# Wi-Fi.net
KiCad netlist of a schematic drawn in Altium Designer
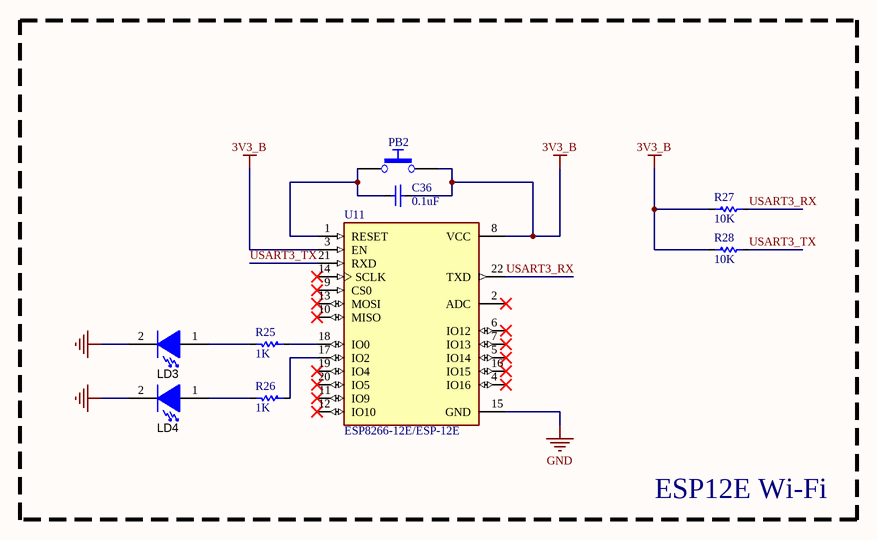
[diagram p0: Wi-Fi.SchDoc]

(export (version "E")
  (design (tool "Eeschema 10.0.6"))
  (components
    (comp (ref "C36")
      (value "0.1uF")
      (footprint "CAPC1608-0603X85N")
      (description "CAP CER 0.1UF 25V X7R 0603")
      (fields (field (name "MANUFACTURER") "Yageo") (field (name "VOLTAGE") "25V"))
      (libsource (lib "capacitor") (part "Capacitor Ceramic"))
    )
    (comp (ref "LD3")
      (value "160-1183-1-ND")
      (footprint "LED_LTST-C190")
      (description "LED, Green, SMD")
      (libsource (lib "LED") (part "LTST-C190GKT"))
    )
    (comp (ref "LD4")
      (value "160-1183-1-ND")
      (footprint "LED_LTST-C190")
      (description "LED, Green, SMD")
      (libsource (lib "LED") (part "LTST-C190GKT"))
    )
    (comp (ref "PB2")
      (value "Push Button")
      (footprint "PB_TYCO_FSMSM")
      (description "Push-Button Switch SPDT")
      (fields
        (field (name "PART NUMBER") "PB_TYCO_FSMSM")
        (field (name "MANUFACTURER") "TYCO ELECTRONICS")
        (field (name "AUTHOR") "CERN DEM JLC")
      )
      (libsource (lib "Eletro-mechanical") (part "PB SPST 1NO-2NO"))
    )
    (comp (ref "R25")
      (value "1K")
      (footprint "RESC1608-0603X50N")
      (description "RES SMD 1K OHM 1% 1/10W 0603")
      (fields (field (name "MANUFACTURER") "Panasonic Electronic Components") (field (name "TOLERANCE") "1%"))
      (libsource (lib "resistor") (part "Resistor SMD"))
    )
    (comp (ref "R26")
      (value "1K")
      (footprint "RESC1608-0603X50N")
      (description "RES SMD 1K OHM 1% 1/10W 0603")
      (fields (field (name "MANUFACTURER") "Panasonic Electronic Components") (field (name "TOLERANCE") "1%"))
      (libsource (lib "resistor") (part "Resistor SMD"))
    )
    (comp (ref "R27")
      (value "10K")
      (footprint "RESC1608-0603X50N")
      (description "RES SMD 10K OHM 1% 1/10W 0603")
      (fields (field (name "MANUFACTURER") "Yageo"))
      (libsource (lib "ANTSIS_PASSIVE") (part "RESISTOR 10K"))
    )
    (comp (ref "R28")
      (value "10K")
      (footprint "RESC1608-0603X50N")
      (description "RES SMD 10K OHM 1% 1/10W 0603")
      (fields (field (name "MANUFACTURER") "Yageo"))
      (libsource (lib "ANTSIS_PASSIVE") (part "RESISTOR 10K"))
    )
    (comp (ref "U11")
      (value "ESP8266-12E/ESP-12E")
      (footprint "XCVR_ESP8266-12E/ESP-12E")
      (fields (field (name "MF") "AI-Thinker"))
      (libsource (lib "ESP8266-12E_ESP-12E") (part "ESP8266-12E/ESP-12E"))
    )
  )
  (nets
    (net (code "1") (name "/USART3_RX") (class "Default")
      (node (ref "R27") (pin "2") (pinfunction "2_2") (pintype "passive"))
      (node (ref "U11") (pin "22") (pinfunction "TXD_22") (pintype "output"))
    )
    (net (code "2") (name "/USART3_TX") (class "Default")
      (node (ref "R28") (pin "2") (pinfunction "2_2") (pintype "passive"))
      (node (ref "U11") (pin "21") (pinfunction "RXD_21") (pintype "input"))
    )
    (net (code "3") (name "3V3_B") (class "Default")
      (node (ref "C36") (pin "2") (pinfunction "2_2") (pintype "passive"))
      (node (ref "PB2") (pin "2") (pinfunction "2_2") (pintype "passive"))
      (node (ref "R27") (pin "1") (pinfunction "1_1") (pintype "passive"))
      (node (ref "R28") (pin "1") (pinfunction "1_1") (pintype "passive"))
      (node (ref "U11") (pin "3") (pinfunction "EN_3") (pintype "input"))
      (node (ref "U11") (pin "8") (pinfunction "VCC_8") (pintype "power_in"))
    )
    (net (code "4") (name "GND") (class "Default")
      (node (ref "LD3") (pin "2") (pinfunction "K_2") (pintype "passive"))
      (node (ref "LD4") (pin "2") (pinfunction "K_2") (pintype "passive"))
      (node (ref "U11") (pin "15") (pinfunction "GND_15") (pintype "power_in"))
    )
    (net (code "5") (name "Net-(LD3-A)") (class "Default")
      (node (ref "LD3") (pin "1") (pinfunction "A_1") (pintype "passive"))
      (node (ref "R25") (pin "2") (pinfunction "2_2") (pintype "passive"))
    )
    (net (code "6") (name "Net-(LD4-A)") (class "Default")
      (node (ref "LD4") (pin "1") (pinfunction "A_1") (pintype "passive"))
      (node (ref "R26") (pin "2") (pinfunction "2_2") (pintype "passive"))
    )
    (net (code "7") (name "Net-(U11-IO0)") (class "Default")
      (node (ref "R25") (pin "1") (pinfunction "1_1") (pintype "passive"))
      (node (ref "U11") (pin "18") (pinfunction "IO0_18") (pintype "bidirectional"))
    )
    (net (code "8") (name "Net-(U11-IO2)") (class "Default")
      (node (ref "R26") (pin "1") (pinfunction "1_1") (pintype "passive"))
      (node (ref "U11") (pin "17") (pinfunction "IO2_17") (pintype "bidirectional"))
    )
    (net (code "9") (name "Net-(U11-RESET)") (class "Default")
      (node (ref "C36") (pin "1") (pinfunction "1_1") (pintype "passive"))
      (node (ref "PB2") (pin "1") (pinfunction "1_1") (pintype "passive"))
      (node (ref "U11") (pin "1") (pinfunction "RESET_1") (pintype "input"))
    )
    (net (code "10") (name "unconnected-(U11-ADC-Pad2)") (class "Default")
      (node (ref "U11") (pin "2") (pinfunction "ADC_2") (pintype "passive+no_connect"))
    )
    (net (code "11") (name "unconnected-(U11-CS0-Pad9)") (class "Default")
      (node (ref "U11") (pin "9") (pinfunction "CS0_9") (pintype "input+no_connect"))
    )
    (net (code "12") (name "unconnected-(U11-IO4-Pad19)") (class "Default")
      (node (ref "U11") (pin "19") (pinfunction "IO4_19") (pintype "bidirectional+no_connect"))
    )
    (net (code "13") (name "unconnected-(U11-IO5-Pad20)") (class "Default")
      (node (ref "U11") (pin "20") (pinfunction "IO5_20") (pintype "bidirectional+no_connect"))
    )
    (net (code "14") (name "unconnected-(U11-IO9-Pad11)") (class "Default")
      (node (ref "U11") (pin "11") (pinfunction "IO9_11") (pintype "bidirectional+no_connect"))
    )
    (net (code "15") (name "unconnected-(U11-IO10-Pad12)") (class "Default")
      (node (ref "U11") (pin "12") (pinfunction "IO10_12") (pintype "bidirectional+no_connect"))
    )
    (net (code "16") (name "unconnected-(U11-IO12-Pad6)") (class "Default")
      (node (ref "U11") (pin "6") (pinfunction "IO12_6") (pintype "bidirectional+no_connect"))
    )
    (net (code "17") (name "unconnected-(U11-IO13-Pad7)") (class "Default")
      (node (ref "U11") (pin "7") (pinfunction "IO13_7") (pintype "bidirectional+no_connect"))
    )
    (net (code "18") (name "unconnected-(U11-IO14-Pad5)") (class "Default")
      (node (ref "U11") (pin "5") (pinfunction "IO14_5") (pintype "bidirectional+no_connect"))
    )
    (net (code "19") (name "unconnected-(U11-IO15-Pad16)") (class "Default")
      (node (ref "U11") (pin "16") (pinfunction "IO15_16") (pintype "bidirectional+no_connect"))
    )
    (net (code "20") (name "unconnected-(U11-IO16-Pad4)") (class "Default")
      (node (ref "U11") (pin "4") (pinfunction "IO16_4") (pintype "bidirectional+no_connect"))
    )
    (net (code "21") (name "unconnected-(U11-MISO-Pad10)") (class "Default")
      (node (ref "U11") (pin "10") (pinfunction "MISO_10") (pintype "bidirectional+no_connect"))
    )
    (net (code "22") (name "unconnected-(U11-MOSI-Pad13)") (class "Default")
      (node (ref "U11") (pin "13") (pinfunction "MOSI_13") (pintype "bidirectional+no_connect"))
    )
    (net (code "23") (name "unconnected-(U11-SCLK-Pad14)") (class "Default")
      (node (ref "U11") (pin "14") (pinfunction "SCLK_14") (pintype "input+no_connect"))
    )
  )
)
